# MC33797.net
KiCad netlist of a schematic drawn in Altium Designer
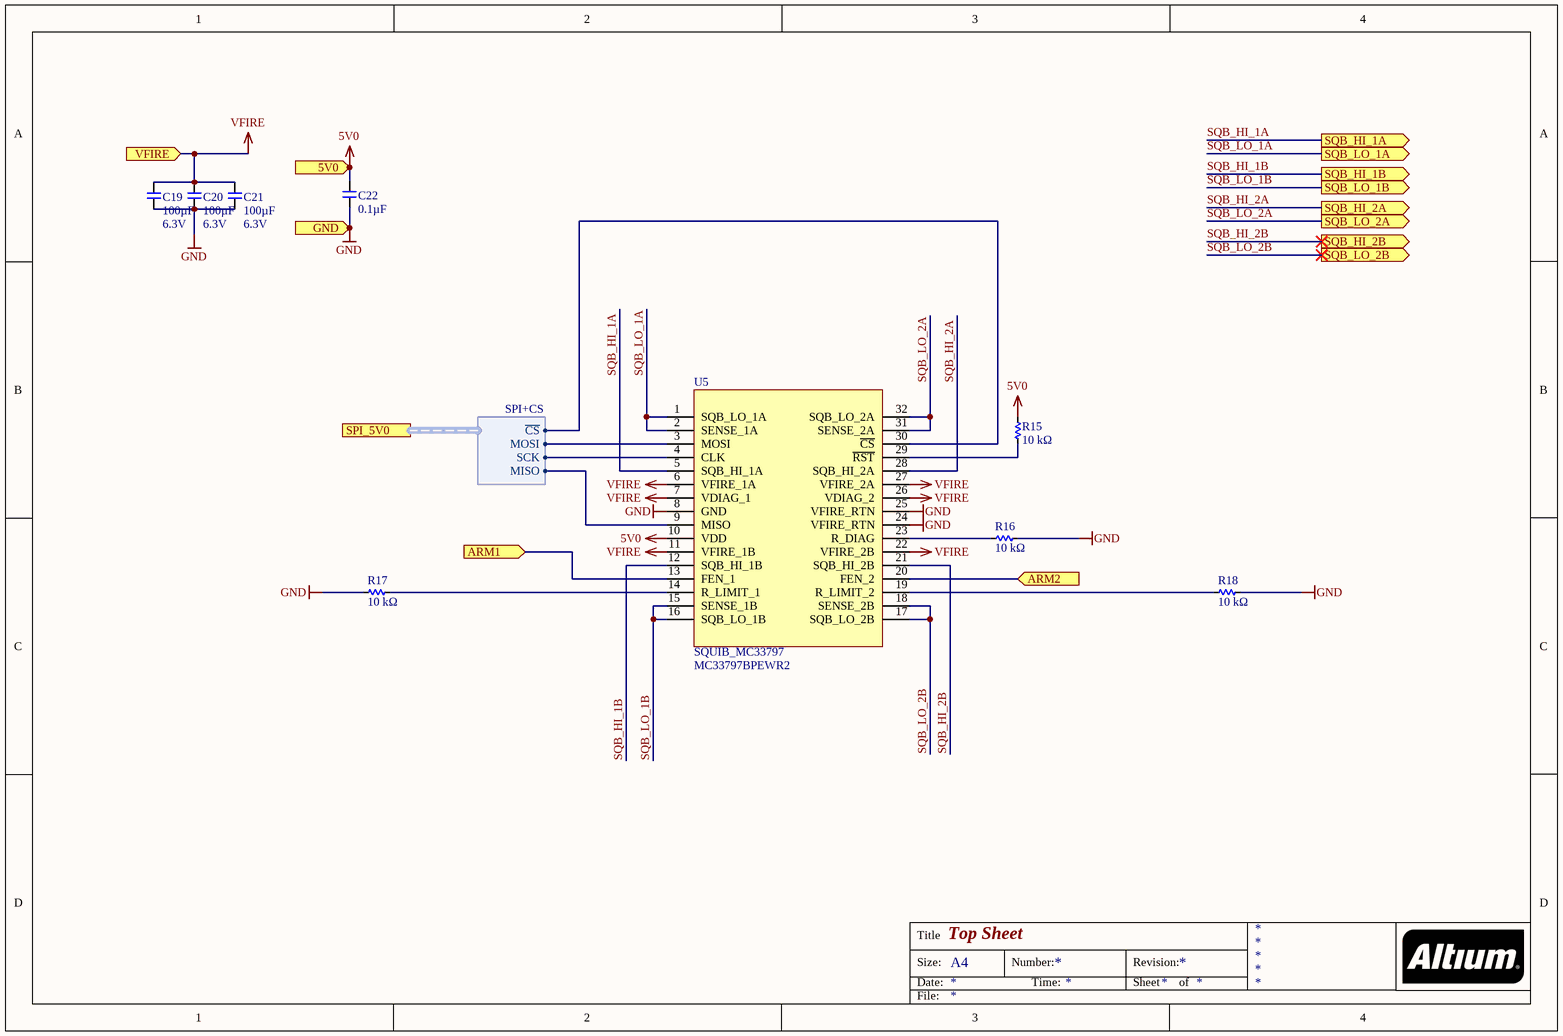
[diagram p0: MC33797.SchDoc]

(export (version "E")
  (design (tool "Eeschema 10.0.6"))
  (components
    (comp (ref "C19")
      (value "CAP_100UF_1206_SMD")
      (footprint "C1206")
      (description "100UF SMD CAP CERAMIC")
      (fields
        (field (name "MANUFACTURER") "Murata Electronics North America")
        (field (name "MANUFACTURER PART NUMBER") "GRM31CD80J107ME39L")
        (field (name "CAPACITANCE") "100µF")
        (field (name "VOLTAGE - RATED") "6.3V")
      )
      (libsource (lib "SSI") (part "CAP_100UF_1206_SMD"))
    )
    (comp (ref "C20")
      (value "CAP_100UF_1206_SMD")
      (footprint "C1206")
      (description "100UF SMD CAP CERAMIC")
      (fields
        (field (name "MANUFACTURER") "Murata Electronics North America")
        (field (name "MANUFACTURER PART NUMBER") "GRM31CD80J107ME39L")
        (field (name "CAPACITANCE") "100µF")
        (field (name "VOLTAGE - RATED") "6.3V")
      )
      (libsource (lib "SSI") (part "CAP_100UF_1206_SMD"))
    )
    (comp (ref "C21")
      (value "CAP_100UF_1206_SMD")
      (footprint "C1206")
      (description "100UF SMD CAP CERAMIC")
      (fields
        (field (name "MANUFACTURER") "Murata Electronics North America")
        (field (name "MANUFACTURER PART NUMBER") "GRM31CD80J107ME39L")
        (field (name "CAPACITANCE") "100µF")
        (field (name "VOLTAGE - RATED") "6.3V")
      )
      (libsource (lib "SSI") (part "CAP_100UF_1206_SMD"))
    )
    (comp (ref "C22")
      (value "__template_cap")
      (footprint "C0603")
      (description "CAP CER 0603 0.1µF X7R 50V 10%")
      (fields
        (field (name "CAPACITANCE (SHORTHAND)") "0.1µF")
        (field (name "MANUFACTURER") "Murata Electronics North America")
      )
      (libsource (lib "passives") (part "__template_cap"))
    )
    (comp (ref "R15")
      (value "__template_resistor")
      (footprint "R0603")
      (description "RES SMD 10K OHM 1% 1/10W 0603")
      (fields
        (field (name "RESISTANCE") "10 kΩ")
        (field (name "MANUFACTURER PART NUMBER") "RC0603FR-0710KL")
        (field (name "MANUFACTURER") "Yageo")
      )
      (libsource (lib "passives") (part "__template_resistor"))
    )
    (comp (ref "R16")
      (value "__template_resistor")
      (footprint "R0603")
      (description "RES SMD 10K OHM 1% 1/10W 0603")
      (fields
        (field (name "RESISTANCE") "10 kΩ")
        (field (name "MANUFACTURER PART NUMBER") "RC0603FR-0710KL")
        (field (name "MANUFACTURER") "Yageo")
      )
      (libsource (lib "passives") (part "__template_resistor"))
    )
    (comp (ref "R17")
      (value "__template_resistor")
      (footprint "R0603")
      (description "RES SMD 10K OHM 1% 1/10W 0603")
      (fields
        (field (name "RESISTANCE") "10 kΩ")
        (field (name "MANUFACTURER PART NUMBER") "RC0603FR-0710KL")
        (field (name "MANUFACTURER") "Yageo")
      )
      (libsource (lib "passives") (part "__template_resistor"))
    )
    (comp (ref "R18")
      (value "__template_resistor")
      (footprint "R0603")
      (description "RES SMD 10K OHM 1% 1/10W 0603")
      (fields
        (field (name "RESISTANCE") "10 kΩ")
        (field (name "MANUFACTURER PART NUMBER") "RC0603FR-0710KL")
        (field (name "MANUFACTURER") "Yageo")
      )
      (libsource (lib "passives") (part "__template_resistor"))
    )
    (comp (ref "U5")
      (value "SQUIB_MC33797")
      (footprint "SOT1762-1")
      (fields
        (field (name "MANUFACTURER") "NXP USA Inc.")
        (field (name "MANUFACTURER PART NUMBER") "MC33797BPEWR2")
      )
      (libsource (lib "SSI") (part "SQUIB_MC33797"))
    )
  )
  (nets
    (net (code "2") (name "/ARM1") (class "Default")
      (node (ref "U5") (pin "13") (pinfunction "FEN_1_13") (pintype "passive"))
    )
    (net (code "3") (name "/ARM2") (class "Default")
      (node (ref "U5") (pin "20") (pinfunction "FEN_2_20") (pintype "passive"))
    )
    (net (code "4") (name "/MISO") (class "Default")
      (node (ref "U5") (pin "9") (pinfunction "MISO_9") (pintype "passive"))
    )
    (net (code "5") (name "/MOSI") (class "Default")
      (node (ref "U5") (pin "3") (pinfunction "MOSI_3") (pintype "passive"))
    )
    (net (code "6") (name "/SCK") (class "Default")
      (node (ref "U5") (pin "4") (pinfunction "CLK_4") (pintype "passive"))
    )
    (net (code "7") (name "/SQB_HI_1A") (class "Default")
      (node (ref "U5") (pin "5") (pinfunction "SQB_HI_1A_5") (pintype "passive"))
    )
    (net (code "8") (name "/SQB_HI_1B") (class "Default")
      (node (ref "U5") (pin "12") (pinfunction "SQB_HI_1B_12") (pintype "passive"))
    )
    (net (code "9") (name "/SQB_HI_2A") (class "Default")
      (node (ref "U5") (pin "28") (pinfunction "SQB_HI_2A_28") (pintype "passive"))
    )
    (net (code "10") (name "/SQB_HI_2B") (class "Default")
      (node (ref "U5") (pin "21") (pinfunction "SQB_HI_2B_21") (pintype "passive"))
    )
    (net (code "11") (name "/SQB_LO_1A") (class "Default")
      (node (ref "U5") (pin "1") (pinfunction "SQB_LO_1A_1") (pintype "passive"))
      (node (ref "U5") (pin "2") (pinfunction "SENSE_1A_2") (pintype "passive"))
    )
    (net (code "12") (name "/SQB_LO_1B") (class "Default")
      (node (ref "U5") (pin "15") (pinfunction "SENSE_1B_15") (pintype "passive"))
      (node (ref "U5") (pin "16") (pinfunction "SQB_LO_1B_16") (pintype "passive"))
    )
    (net (code "13") (name "/SQB_LO_2A") (class "Default")
      (node (ref "U5") (pin "31") (pinfunction "SENSE_2A_31") (pintype "passive"))
      (node (ref "U5") (pin "32") (pinfunction "SQB_LO_2A_32") (pintype "passive"))
    )
    (net (code "14") (name "/SQB_LO_2B") (class "Default")
      (node (ref "U5") (pin "17") (pinfunction "SQB_LO_2B_17") (pintype "passive"))
      (node (ref "U5") (pin "18") (pinfunction "SENSE_2B_18") (pintype "passive"))
    )
    (net (code "16") (name "/~{CS}") (class "Default")
      (node (ref "U5") (pin "30") (pinfunction "~{CS}_30") (pintype "passive"))
    )
    (net (code "17") (name "5V0") (class "Default")
      (node (ref "C22") (pin "1") (pintype "passive"))
      (node (ref "R15") (pin "2") (pintype "passive"))
      (node (ref "U5") (pin "10") (pinfunction "VDD_10") (pintype "passive"))
    )
    (net (code "18") (name "GND") (class "Default")
      (node (ref "C19") (pin "2") (pintype "passive"))
      (node (ref "C20") (pin "2") (pintype "passive"))
      (node (ref "C21") (pin "2") (pintype "passive"))
      (node (ref "C22") (pin "2") (pintype "passive"))
      (node (ref "R16") (pin "2") (pintype "passive"))
      (node (ref "R17") (pin "1") (pintype "passive"))
      (node (ref "R18") (pin "2") (pintype "passive"))
      (node (ref "U5") (pin "24") (pinfunction "VFIRE_RTN_24") (pintype "passive"))
      (node (ref "U5") (pin "25") (pinfunction "VFIRE_RTN_25") (pintype "passive"))
      (node (ref "U5") (pin "8") (pinfunction "GND_8") (pintype "passive"))
    )
    (net (code "19") (name "Net-(U5-R_DIAG)") (class "Default")
      (node (ref "R16") (pin "1") (pintype "passive"))
      (node (ref "U5") (pin "23") (pinfunction "R_DIAG_23") (pintype "passive"))
    )
    (net (code "20") (name "Net-(U5-R_LIMIT_1)") (class "Default")
      (node (ref "R17") (pin "2") (pintype "passive"))
      (node (ref "U5") (pin "14") (pinfunction "R_LIMIT_1_14") (pintype "passive"))
    )
    (net (code "21") (name "Net-(U5-R_LIMIT_2)") (class "Default")
      (node (ref "R18") (pin "1") (pintype "passive"))
      (node (ref "U5") (pin "19") (pinfunction "R_LIMIT_2_19") (pintype "passive"))
    )
    (net (code "22") (name "Net-(U5-~{RST})") (class "Default")
      (node (ref "R15") (pin "1") (pintype "passive"))
      (node (ref "U5") (pin "29") (pinfunction "~{RST}_29") (pintype "passive"))
    )
    (net (code "23") (name "VFIRE") (class "Default")
      (node (ref "C19") (pin "1") (pintype "passive"))
      (node (ref "C20") (pin "1") (pintype "passive"))
      (node (ref "C21") (pin "1") (pintype "passive"))
      (node (ref "U5") (pin "11") (pinfunction "VFIRE_1B_11") (pintype "passive"))
      (node (ref "U5") (pin "22") (pinfunction "VFIRE_2B_22") (pintype "passive"))
      (node (ref "U5") (pin "26") (pinfunction "VDIAG_2_26") (pintype "passive"))
      (node (ref "U5") (pin "27") (pinfunction "VFIRE_2A_27") (pintype "passive"))
      (node (ref "U5") (pin "6") (pinfunction "VFIRE_1A_6") (pintype "passive"))
      (node (ref "U5") (pin "7") (pinfunction "VDIAG_1_7") (pintype "passive"))
    )
  )
)
